# Christmas_Star.net
KiCad netlist of a schematic drawn in EAGLE
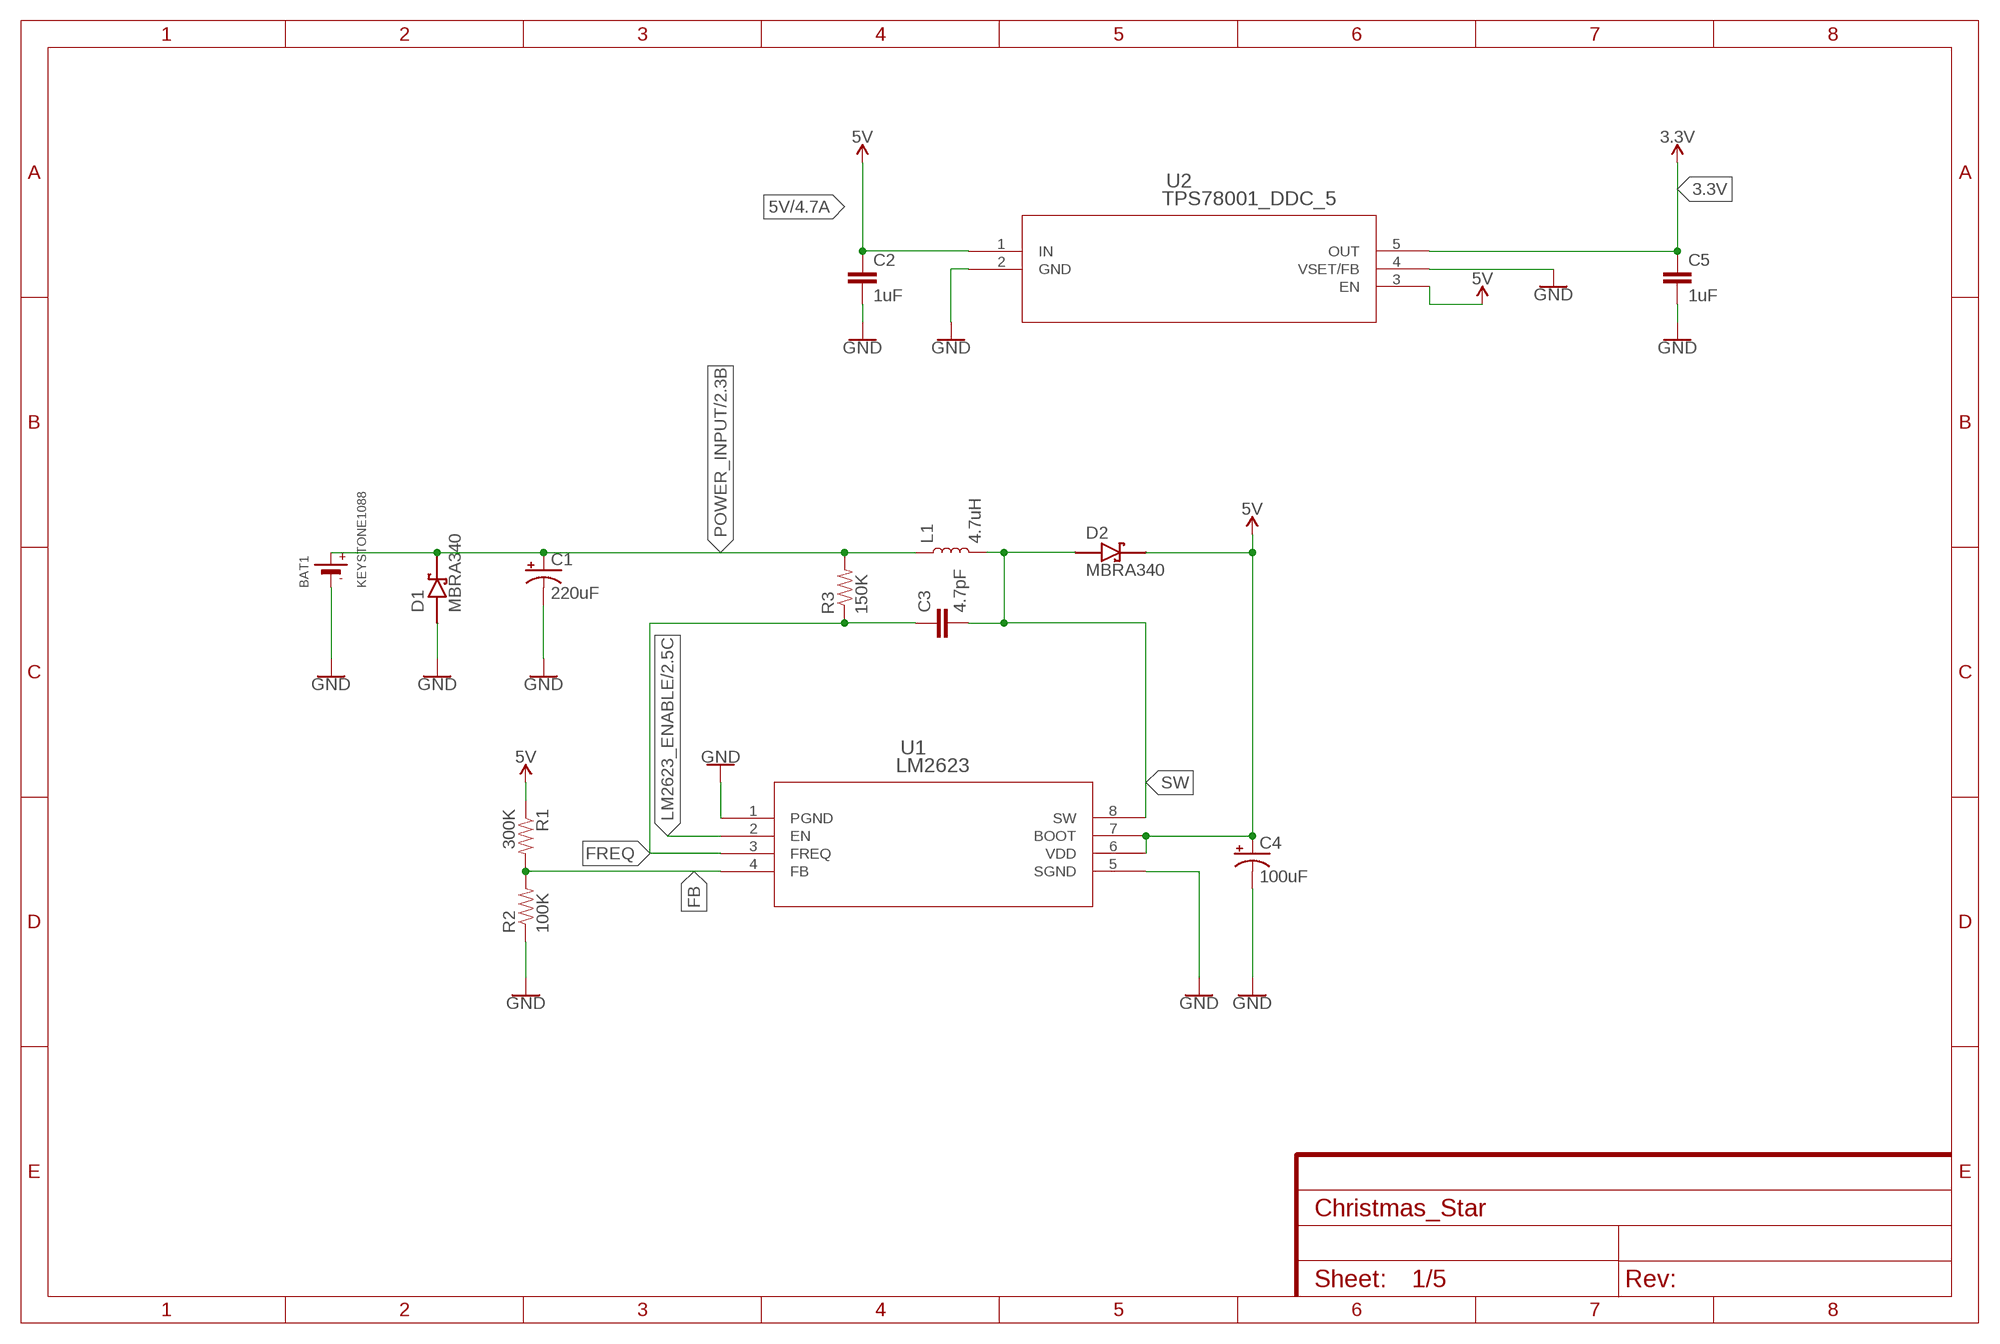
[diagram p0: schematic, sheet 1]
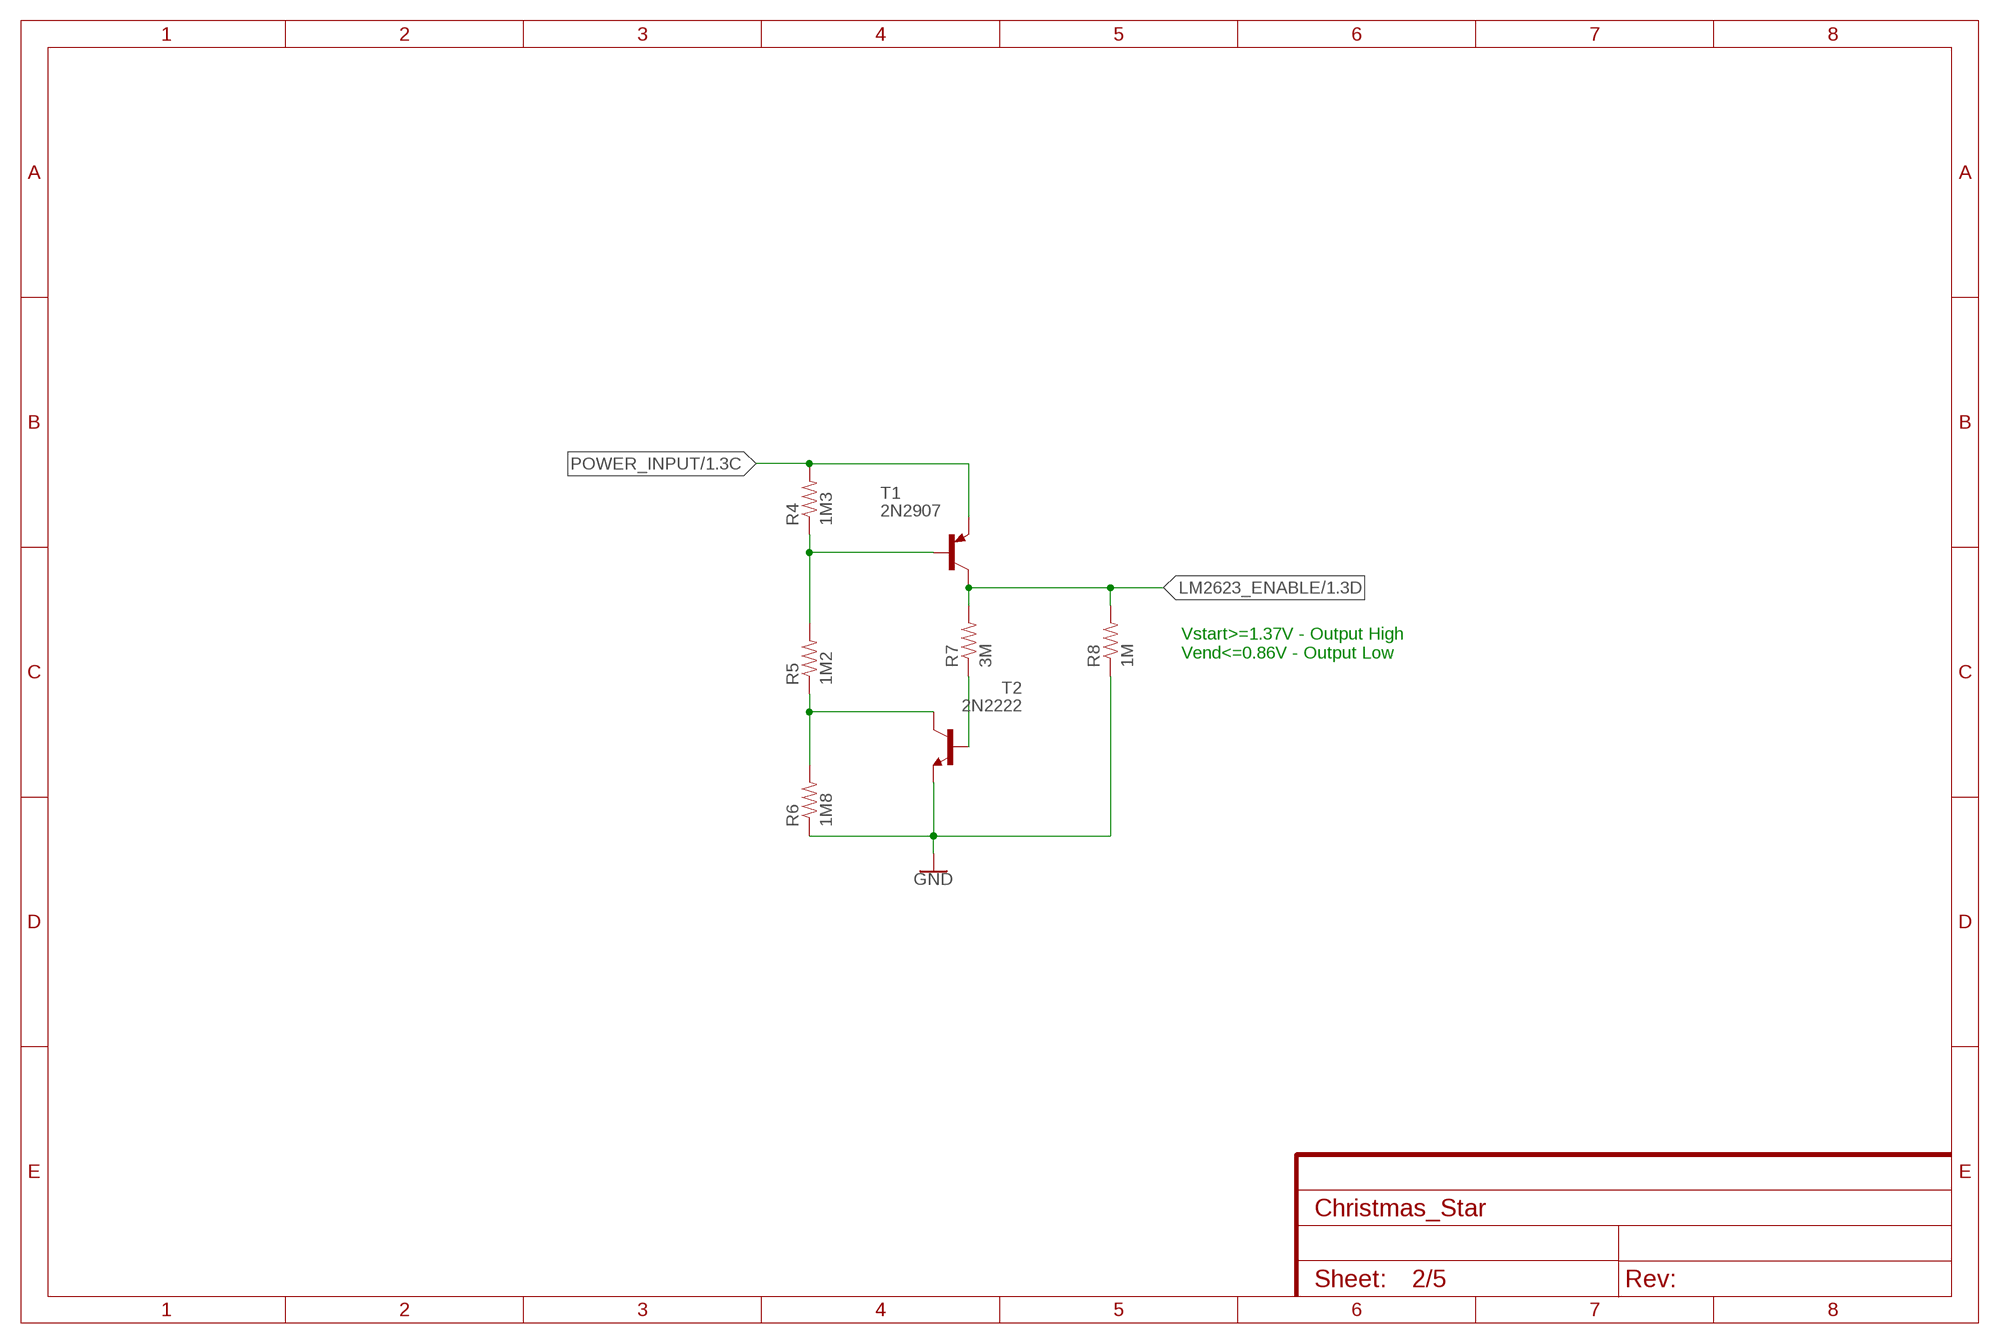
[diagram p1: schematic, sheet 2]
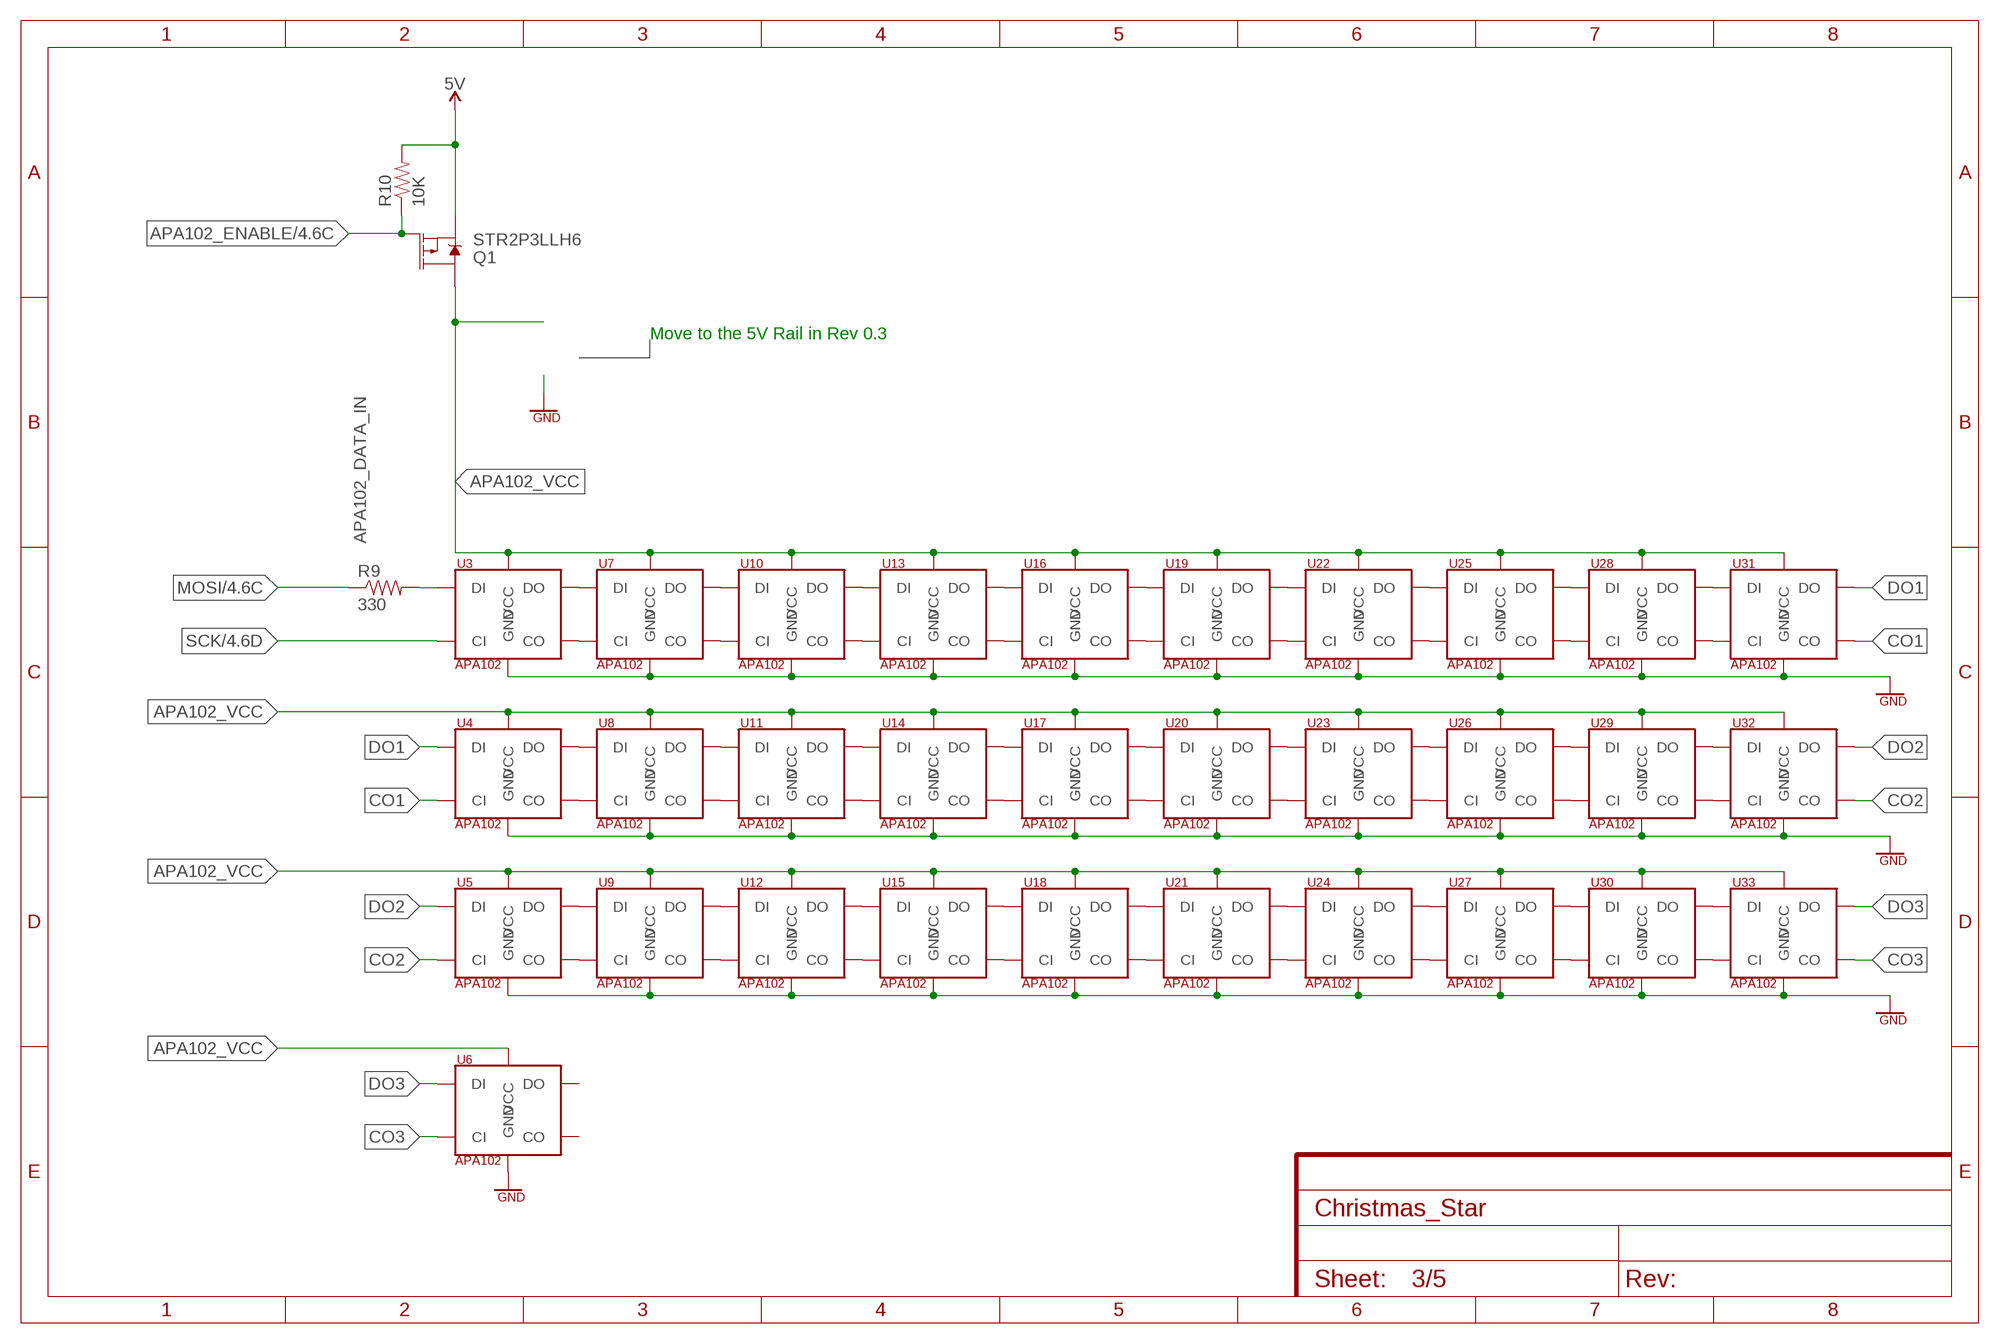
[diagram p2: schematic, sheet 3]
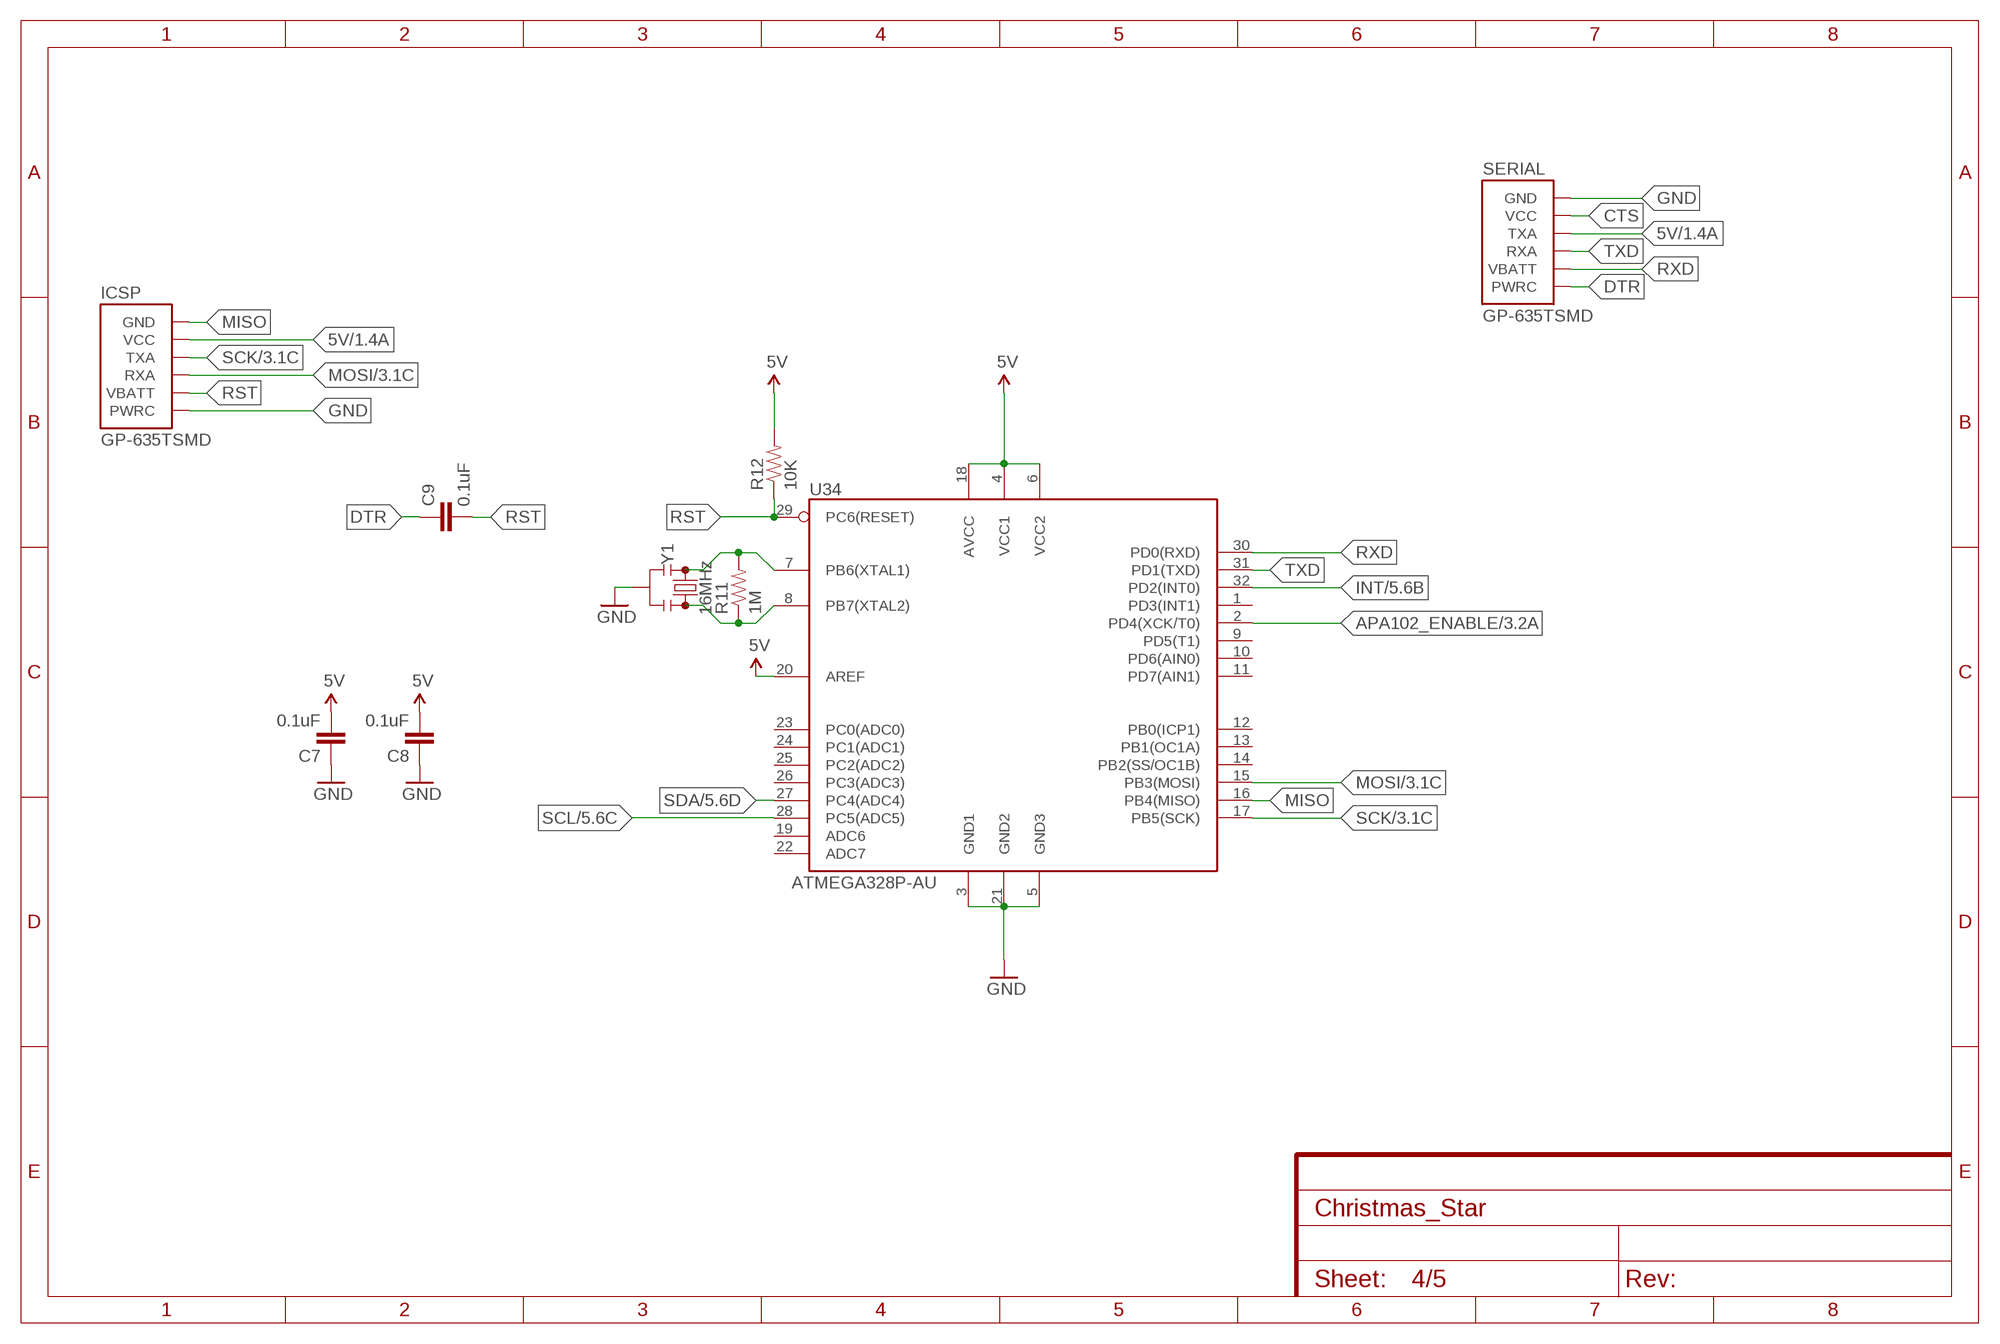
[diagram p3: schematic, sheet 4]
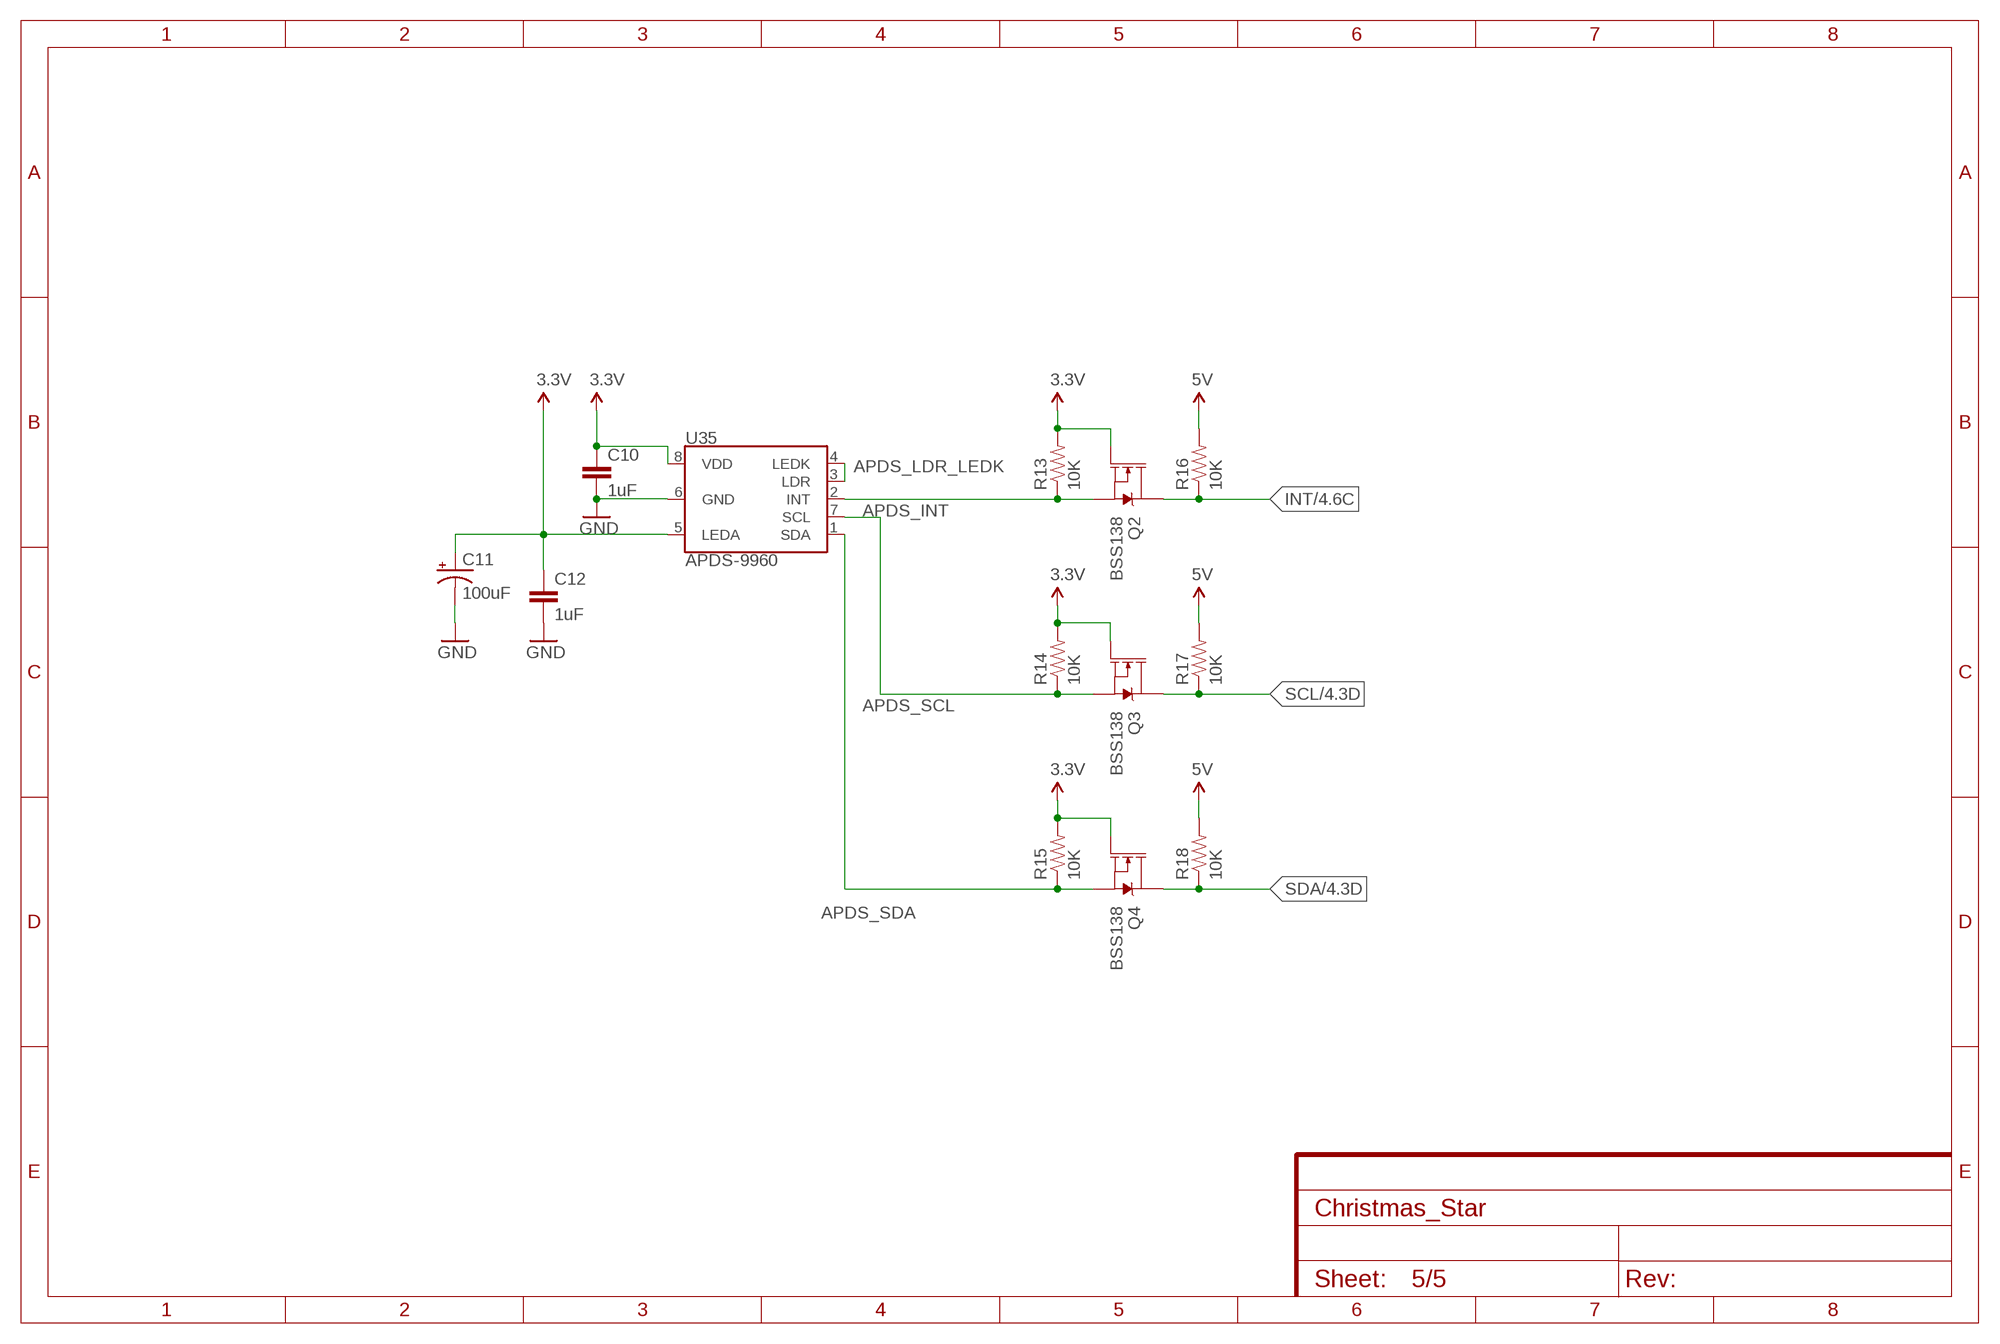
[diagram p4: schematic, sheet 5]

(export (version "E")
  (design (tool "Eeschema 10.0.6"))
  (components
    (comp (ref "Q1")
      (value "STR2P3LLH6")
      (footprint "eagle-import:SOT23-3")
      (libsource (lib "eagle-import") (part "MOSFET_PCH-IRLML2244"))
    )
    (comp (ref "R9")
      (value "330")
      (footprint "eagle-import:0603-RES")
      (libsource (lib "eagle-import") (part "RESISTOR0603-RES"))
    )
    (comp (ref "R10")
      (value "10K")
      (footprint "eagle-import:0603-RES")
      (libsource (lib "eagle-import") (part "RESISTOR0603-RES"))
    )
    (comp (ref "U3")
      (value "APA102")
      (footprint "eagle-import:APA102_2020")
      (libsource (lib "eagle-import") (part "APA1022020"))
    )
    (comp (ref "U4")
      (value "APA102")
      (footprint "eagle-import:APA102_2020")
      (libsource (lib "eagle-import") (part "APA1022020"))
    )
    (comp (ref "U5")
      (value "APA102")
      (footprint "eagle-import:APA102_2020")
      (libsource (lib "eagle-import") (part "APA1022020"))
    )
    (comp (ref "U6")
      (value "APA102")
      (footprint "eagle-import:APA102_2020")
      (libsource (lib "eagle-import") (part "APA1022020"))
    )
    (comp (ref "U7")
      (value "APA102")
      (footprint "eagle-import:APA102_2020")
      (libsource (lib "eagle-import") (part "APA1022020"))
    )
    (comp (ref "U8")
      (value "APA102")
      (footprint "eagle-import:APA102_2020")
      (libsource (lib "eagle-import") (part "APA1022020"))
    )
    (comp (ref "U9")
      (value "APA102")
      (footprint "eagle-import:APA102_2020")
      (libsource (lib "eagle-import") (part "APA1022020"))
    )
    (comp (ref "U10")
      (value "APA102")
      (footprint "eagle-import:APA102_2020")
      (libsource (lib "eagle-import") (part "APA1022020"))
    )
    (comp (ref "U11")
      (value "APA102")
      (footprint "eagle-import:APA102_2020")
      (libsource (lib "eagle-import") (part "APA1022020"))
    )
    (comp (ref "U12")
      (value "APA102")
      (footprint "eagle-import:APA102_2020")
      (libsource (lib "eagle-import") (part "APA1022020"))
    )
    (comp (ref "U13")
      (value "APA102")
      (footprint "eagle-import:APA102_2020")
      (libsource (lib "eagle-import") (part "APA1022020"))
    )
    (comp (ref "U14")
      (value "APA102")
      (footprint "eagle-import:APA102_2020")
      (libsource (lib "eagle-import") (part "APA1022020"))
    )
    (comp (ref "U15")
      (value "APA102")
      (footprint "eagle-import:APA102_2020")
      (libsource (lib "eagle-import") (part "APA1022020"))
    )
    (comp (ref "U16")
      (value "APA102")
      (footprint "eagle-import:APA102_2020")
      (libsource (lib "eagle-import") (part "APA1022020"))
    )
    (comp (ref "U17")
      (value "APA102")
      (footprint "eagle-import:APA102_2020")
      (libsource (lib "eagle-import") (part "APA1022020"))
    )
    (comp (ref "U18")
      (value "APA102")
      (footprint "eagle-import:APA102_2020")
      (libsource (lib "eagle-import") (part "APA1022020"))
    )
    (comp (ref "U19")
      (value "APA102")
      (footprint "eagle-import:APA102_2020")
      (libsource (lib "eagle-import") (part "APA1022020"))
    )
    (comp (ref "U20")
      (value "APA102")
      (footprint "eagle-import:APA102_2020")
      (libsource (lib "eagle-import") (part "APA1022020"))
    )
    (comp (ref "U21")
      (value "APA102")
      (footprint "eagle-import:APA102_2020")
      (libsource (lib "eagle-import") (part "APA1022020"))
    )
    (comp (ref "U22")
      (value "APA102")
      (footprint "eagle-import:APA102_2020")
      (libsource (lib "eagle-import") (part "APA1022020"))
    )
    (comp (ref "U23")
      (value "APA102")
      (footprint "eagle-import:APA102_2020")
      (libsource (lib "eagle-import") (part "APA1022020"))
    )
    (comp (ref "U24")
      (value "APA102")
      (footprint "eagle-import:APA102_2020")
      (libsource (lib "eagle-import") (part "APA1022020"))
    )
    (comp (ref "U25")
      (value "APA102")
      (footprint "eagle-import:APA102_2020")
      (libsource (lib "eagle-import") (part "APA1022020"))
    )
    (comp (ref "U26")
      (value "APA102")
      (footprint "eagle-import:APA102_2020")
      (libsource (lib "eagle-import") (part "APA1022020"))
    )
    (comp (ref "U27")
      (value "APA102")
      (footprint "eagle-import:APA102_2020")
      (libsource (lib "eagle-import") (part "APA1022020"))
    )
    (comp (ref "U28")
      (value "APA102")
      (footprint "eagle-import:APA102_2020")
      (libsource (lib "eagle-import") (part "APA1022020"))
    )
    (comp (ref "U29")
      (value "APA102")
      (footprint "eagle-import:APA102_2020")
      (libsource (lib "eagle-import") (part "APA1022020"))
    )
    (comp (ref "U30")
      (value "APA102")
      (footprint "eagle-import:APA102_2020")
      (libsource (lib "eagle-import") (part "APA1022020"))
    )
    (comp (ref "U31")
      (value "APA102")
      (footprint "eagle-import:APA102_2020")
      (libsource (lib "eagle-import") (part "APA1022020"))
    )
    (comp (ref "U32")
      (value "APA102")
      (footprint "eagle-import:APA102_2020")
      (libsource (lib "eagle-import") (part "APA1022020"))
    )
    (comp (ref "U33")
      (value "APA102")
      (footprint "eagle-import:APA102_2020")
      (libsource (lib "eagle-import") (part "APA1022020"))
    )
    (comp (ref "C10")
      (value "1uF")
      (footprint "eagle-import:0603-CAP")
      (libsource (lib "eagle-import") (part "SparkFun-Passives_CAP0603-CAP"))
    )
    (comp (ref "C11")
      (value "100uF")
      (footprint "eagle-import:EIA3216-KIT")
      (libsource (lib "eagle-import") (part "CAP_POL1206-KIT"))
    )
    (comp (ref "C12")
      (value "1uF")
      (footprint "eagle-import:0603-CAP")
      (libsource (lib "eagle-import") (part "SparkFun-Passives_CAP0603-CAP"))
    )
    (comp (ref "Q2")
      (value "BSS138")
      (footprint "eagle-import:SOT23-3")
      (libsource (lib "eagle-import") (part "MOSFET-NCH-BSS138"))
    )
    (comp (ref "Q3")
      (value "BSS138")
      (footprint "eagle-import:SOT23-3")
      (libsource (lib "eagle-import") (part "MOSFET-NCH-BSS138"))
    )
    (comp (ref "Q4")
      (value "BSS138")
      (footprint "eagle-import:SOT23-3")
      (libsource (lib "eagle-import") (part "MOSFET-NCH-BSS138"))
    )
    (comp (ref "R13")
      (value "10K")
      (footprint "eagle-import:0603-RES")
      (libsource (lib "eagle-import") (part "RESISTOR0603-RES"))
    )
    (comp (ref "R14")
      (value "10K")
      (footprint "eagle-import:0603-RES")
      (libsource (lib "eagle-import") (part "RESISTOR0603-RES"))
    )
    (comp (ref "R15")
      (value "10K")
      (footprint "eagle-import:0603-RES")
      (libsource (lib "eagle-import") (part "RESISTOR0603-RES"))
    )
    (comp (ref "R16")
      (value "10K")
      (footprint "eagle-import:0603-RES")
      (libsource (lib "eagle-import") (part "RESISTOR0603-RES"))
    )
    (comp (ref "R17")
      (value "10K")
      (footprint "eagle-import:0603-RES")
      (libsource (lib "eagle-import") (part "RESISTOR0603-RES"))
    )
    (comp (ref "R18")
      (value "10K")
      (footprint "eagle-import:0603-RES")
      (libsource (lib "eagle-import") (part "RESISTOR0603-RES"))
    )
    (comp (ref "U35")
      (value "APDS-9960")
      (footprint "eagle-import:APDS-9960")
      (libsource (lib "eagle-import") (part "APDS-9960"))
    )
    (comp (ref "BAT1")
      (value "KEYSTONE1088")
      (footprint "eagle-import:KEYSTONE1088")
      (libsource (lib "eagle-import") (part "KEYSTONE1088"))
    )
    (comp (ref "C1")
      (value "220uF")
      (footprint "eagle-import:EIA3528-KIT")
      (libsource (lib "eagle-import") (part "SparkFun-Passives_CAP_POL3528-KIT"))
    )
    (comp (ref "C2")
      (value "1uF")
      (footprint "eagle-import:0603-CAP")
      (libsource (lib "eagle-import") (part "SparkFun-Passives_CAP0603-CAP"))
    )
    (comp (ref "C3")
      (value "4.7pF")
      (footprint "eagle-import:0603-CAP")
      (libsource (lib "eagle-import") (part "CAP0603-CAP"))
    )
    (comp (ref "C4")
      (value "100uF")
      (footprint "eagle-import:EIA3216-KIT")
      (libsource (lib "eagle-import") (part "SparkFun-Passives_CAP_POL1206-KIT"))
    )
    (comp (ref "C5")
      (value "1uF")
      (footprint "eagle-import:0603-CAP")
      (libsource (lib "eagle-import") (part "SparkFun-Passives_CAP0603-CAP"))
    )
    (comp (ref "D1")
      (value "MBRA340")
      (footprint "eagle-import:DIOM4427X270N")
      (fields (field (name "MANUFACTURER") "Fairchild Semiconductor"))
      (libsource (lib "eagle-import") (part "SS12"))
    )
    (comp (ref "D2")
      (value "MBRA340")
      (footprint "eagle-import:DIOM4427X270N")
      (fields (field (name "MANUFACTURER") "Fairchild Semiconductor"))
      (libsource (lib "eagle-import") (part "SS12"))
    )
    (comp (ref "L1")
      (value "4.7uH")
      (footprint "eagle-import:LTF5022")
      (libsource (lib "eagle-import") (part "INDUCTOR"))
    )
    (comp (ref "R1")
      (value "300K")
      (footprint "eagle-import:0603-RES")
      (libsource (lib "eagle-import") (part "RESISTOR0603-RES"))
    )
    (comp (ref "R2")
      (value "100K")
      (footprint "eagle-import:0603-RES")
      (libsource (lib "eagle-import") (part "RESISTOR0603-RES"))
    )
    (comp (ref "R3")
      (value "150K")
      (footprint "eagle-import:0603-RES")
      (libsource (lib "eagle-import") (part "RESISTOR0603-RES"))
    )
    (comp (ref "U1")
      (value "LM2623")
      (footprint "eagle-import:MUA08A")
      (fields (field (name "MANUFACTURER_PART_NUMBER") "lm2623ammnopb"))
      (libsource (lib "eagle-import") (part "LM2623_DGK_8"))
    )
    (comp (ref "U2")
      (value "TPS78001_DDC_5")
      (footprint "eagle-import:DDC5")
      (fields
        (field (name "GENERIC_PART_NUMBER") "TPS78001")
        (field (name "MANUFACTURER") "Texas Instruments")
        (field (name "MANUFACTURER_PART_NUMBER") "tps78001_ddc_5")
      )
      (libsource (lib "eagle-import") (part "TPS78001_DDC_5"))
    )
    (comp (ref "R4")
      (value "1M3")
      (footprint "eagle-import:0603-RES")
      (libsource (lib "eagle-import") (part "RESISTOR0603-RES"))
    )
    (comp (ref "R5")
      (value "1M2")
      (footprint "eagle-import:0603-RES")
      (libsource (lib "eagle-import") (part "RESISTOR0603-RES"))
    )
    (comp (ref "R6")
      (value "1M8")
      (footprint "eagle-import:0603-RES")
      (libsource (lib "eagle-import") (part "RESISTOR0603-RES"))
    )
    (comp (ref "R7")
      (value "3M")
      (footprint "eagle-import:0603-RES")
      (libsource (lib "eagle-import") (part "RESISTOR0603-RES"))
    )
    (comp (ref "R8")
      (value "1M")
      (footprint "eagle-import:0603-RES")
      (libsource (lib "eagle-import") (part "RESISTOR0603-RES"))
    )
    (comp (ref "T1")
      (value "2N2907")
      (footprint "eagle-import:SOT23-BEC")
      (libsource (lib "eagle-import") (part "-PNP-SOT23-BECMMBT2907ALT1"))
    )
    (comp (ref "T2")
      (value "2N2222")
      (footprint "eagle-import:SOT23-BEC")
      (libsource (lib "eagle-import") (part "-NPN-SOT23-BECMMBT2222ALT1"))
    )
    (comp (ref "C7")
      (value "0.1uF")
      (footprint "eagle-import:0603-CAP")
      (libsource (lib "eagle-import") (part "SparkFun-Passives_CAP0603-CAP"))
    )
    (comp (ref "C8")
      (value "0.1uF")
      (footprint "eagle-import:0603-CAP")
      (libsource (lib "eagle-import") (part "SparkFun-Passives_CAP0603-CAP"))
    )
    (comp (ref "C9")
      (value "0.1uF")
      (footprint "eagle-import:0603-CAP")
      (libsource (lib "eagle-import") (part "SparkFun-Passives_CAP0603-CAP"))
    )
    (comp (ref "ICSP")
      (value "GP-635TSMD")
      (footprint "eagle-import:GP-635T")
      (libsource (lib "eagle-import") (part "GP-635TSMD"))
    )
    (comp (ref "R11")
      (value "1M")
      (footprint "eagle-import:0603-RES")
      (libsource (lib "eagle-import") (part "RESISTOR0603-RES"))
    )
    (comp (ref "R12")
      (value "10K")
      (footprint "eagle-import:0603-RES")
      (libsource (lib "eagle-import") (part "RESISTOR0603-RES"))
    )
    (comp (ref "SERIAL")
      (value "GP-635TSMD")
      (footprint "eagle-import:GP-635T")
      (libsource (lib "eagle-import") (part "GP-635TSMD"))
    )
    (comp (ref "U34")
      (value "ATMEGA328P-AU")
      (footprint "eagle-import:TQFP32")
      (libsource (lib "eagle-import") (part "ATMEGA328P-AU"))
    )
    (comp (ref "Y1")
      (value "16MHz")
      (footprint "eagle-import:RESONATOR-SMD-3.2X1.3")
      (libsource (lib "eagle-import") (part "RESONATOR-16MHZSMD_3.2X1.3"))
    )
  )
  (nets
    (net (code "1") (name "3.3V") (class "Default")
      (node (ref "C10") (pin "1") (pinfunction "1_1") (pintype "passive"))
      (node (ref "C11") (pin "A") (pinfunction "+_A") (pintype "passive"))
      (node (ref "C12") (pin "1") (pinfunction "1_1") (pintype "passive"))
      (node (ref "C5") (pin "1") (pinfunction "1_1") (pintype "passive"))
      (node (ref "Q2") (pin "1") (pinfunction "G_1") (pintype "bidirectional"))
      (node (ref "Q3") (pin "1") (pinfunction "G_1") (pintype "bidirectional"))
      (node (ref "Q4") (pin "1") (pinfunction "G_1") (pintype "bidirectional"))
      (node (ref "R13") (pin "2") (pinfunction "2_2") (pintype "passive"))
      (node (ref "R14") (pin "2") (pinfunction "2_2") (pintype "passive"))
      (node (ref "R15") (pin "2") (pinfunction "2_2") (pintype "passive"))
      (node (ref "U2") (pin "5") (pinfunction "OUT_5") (pintype "output"))
      (node (ref "U35") (pin "5") (pinfunction "LEDA_5") (pintype "bidirectional"))
      (node (ref "U35") (pin "8") (pinfunction "VDD_8") (pintype "bidirectional"))
    )
    (net (code "2") (name "5V") (class "Default")
      (node (ref "C2") (pin "1") (pinfunction "1_1") (pintype "passive"))
      (node (ref "C4") (pin "A") (pinfunction "+_A") (pintype "passive"))
      (node (ref "C7") (pin "2") (pinfunction "2_2") (pintype "passive"))
      (node (ref "C8") (pin "2") (pinfunction "2_2") (pintype "passive"))
      (node (ref "D2") (pin "C") (pinfunction "C_C") (pintype "passive"))
      (node (ref "ICSP") (pin "2") (pinfunction "VCC_2") (pintype "power_in"))
      (node (ref "Q1") (pin "2") (pinfunction "S_2") (pintype "bidirectional"))
      (node (ref "R1") (pin "1") (pinfunction "1_1") (pintype "passive"))
      (node (ref "R10") (pin "2") (pinfunction "2_2") (pintype "passive"))
      (node (ref "R12") (pin "2") (pinfunction "2_2") (pintype "passive"))
      (node (ref "R16") (pin "2") (pinfunction "2_2") (pintype "passive"))
      (node (ref "R17") (pin "2") (pinfunction "2_2") (pintype "passive"))
      (node (ref "R18") (pin "2") (pinfunction "2_2") (pintype "passive"))
      (node (ref "SERIAL") (pin "3") (pinfunction "TXA_3") (pintype "output"))
      (node (ref "U1") (pin "6") (pinfunction "VDD_6") (pintype "power_in"))
      (node (ref "U1") (pin "7") (pinfunction "BOOT_7") (pintype "passive"))
      (node (ref "U2") (pin "1") (pinfunction "IN_1") (pintype "input"))
      (node (ref "U2") (pin "3") (pinfunction "EN_3") (pintype "passive"))
      (node (ref "U34") (pin "18") (pinfunction "AVCC_18") (pintype "bidirectional"))
      (node (ref "U34") (pin "20") (pinfunction "AREF_20") (pintype "bidirectional"))
      (node (ref "U34") (pin "4") (pinfunction "VCC1_4") (pintype "bidirectional"))
      (node (ref "U34") (pin "6") (pinfunction "VCC2_6") (pintype "bidirectional"))
    )
    (net (code "3") (name "APA102_DATA_IN") (class "Default")
      (node (ref "R9") (pin "2") (pinfunction "2_2") (pintype "passive"))
      (node (ref "U3") (pin "D_IN") (pinfunction "DI_D_IN") (pintype "input"))
    )
    (net (code "4") (name "APA102_ENABLE") (class "Default")
      (node (ref "Q1") (pin "1") (pinfunction "G_1") (pintype "bidirectional"))
      (node (ref "R10") (pin "1") (pinfunction "1_1") (pintype "passive"))
      (node (ref "U34") (pin "2") (pinfunction "PD4(XCK/T0)_2") (pintype "bidirectional"))
    )
    (net (code "5") (name "APA102_VCC") (class "Default")
      (node (ref "Q1") (pin "3") (pinfunction "D_3") (pintype "bidirectional"))
      (node (ref "U10") (pin "VCC") (pinfunction "VCC_VCC") (pintype "power_in"))
      (node (ref "U11") (pin "VCC") (pinfunction "VCC_VCC") (pintype "power_in"))
      (node (ref "U12") (pin "VCC") (pinfunction "VCC_VCC") (pintype "power_in"))
      (node (ref "U13") (pin "VCC") (pinfunction "VCC_VCC") (pintype "power_in"))
      (node (ref "U14") (pin "VCC") (pinfunction "VCC_VCC") (pintype "power_in"))
      (node (ref "U15") (pin "VCC") (pinfunction "VCC_VCC") (pintype "power_in"))
      (node (ref "U16") (pin "VCC") (pinfunction "VCC_VCC") (pintype "power_in"))
      (node (ref "U17") (pin "VCC") (pinfunction "VCC_VCC") (pintype "power_in"))
      (node (ref "U18") (pin "VCC") (pinfunction "VCC_VCC") (pintype "power_in"))
      (node (ref "U19") (pin "VCC") (pinfunction "VCC_VCC") (pintype "power_in"))
      (node (ref "U20") (pin "VCC") (pinfunction "VCC_VCC") (pintype "power_in"))
      (node (ref "U21") (pin "VCC") (pinfunction "VCC_VCC") (pintype "power_in"))
      (node (ref "U22") (pin "VCC") (pinfunction "VCC_VCC") (pintype "power_in"))
      (node (ref "U23") (pin "VCC") (pinfunction "VCC_VCC") (pintype "power_in"))
      (node (ref "U24") (pin "VCC") (pinfunction "VCC_VCC") (pintype "power_in"))
      (node (ref "U25") (pin "VCC") (pinfunction "VCC_VCC") (pintype "power_in"))
      (node (ref "U26") (pin "VCC") (pinfunction "VCC_VCC") (pintype "power_in"))
      (node (ref "U27") (pin "VCC") (pinfunction "VCC_VCC") (pintype "power_in"))
      (node (ref "U28") (pin "VCC") (pinfunction "VCC_VCC") (pintype "power_in"))
      (node (ref "U29") (pin "VCC") (pinfunction "VCC_VCC") (pintype "power_in"))
      (node (ref "U3") (pin "VCC") (pinfunction "VCC_VCC") (pintype "power_in"))
      (node (ref "U30") (pin "VCC") (pinfunction "VCC_VCC") (pintype "power_in"))
      (node (ref "U31") (pin "VCC") (pinfunction "VCC_VCC") (pintype "power_in"))
      (node (ref "U32") (pin "VCC") (pinfunction "VCC_VCC") (pintype "power_in"))
      (node (ref "U33") (pin "VCC") (pinfunction "VCC_VCC") (pintype "power_in"))
      (node (ref "U4") (pin "VCC") (pinfunction "VCC_VCC") (pintype "power_in"))
      (node (ref "U5") (pin "VCC") (pinfunction "VCC_VCC") (pintype "power_in"))
      (node (ref "U6") (pin "VCC") (pinfunction "VCC_VCC") (pintype "power_in"))
      (node (ref "U7") (pin "VCC") (pinfunction "VCC_VCC") (pintype "power_in"))
      (node (ref "U8") (pin "VCC") (pinfunction "VCC_VCC") (pintype "power_in"))
      (node (ref "U9") (pin "VCC") (pinfunction "VCC_VCC") (pintype "power_in"))
    )
    (net (code "6") (name "APDS_INT") (class "Default")
      (node (ref "Q2") (pin "2") (pinfunction "S_2") (pintype "bidirectional"))
      (node (ref "R13") (pin "1") (pinfunction "1_1") (pintype "passive"))
      (node (ref "U35") (pin "2") (pinfunction "INT_2") (pintype "bidirectional"))
    )
    (net (code "7") (name "APDS_LDR_LEDK") (class "Default")
      (node (ref "U35") (pin "3") (pinfunction "LDR_3") (pintype "bidirectional"))
      (node (ref "U35") (pin "4") (pinfunction "LEDK_4") (pintype "bidirectional"))
    )
    (net (code "8") (name "APDS_SCL") (class "Default")
      (node (ref "Q3") (pin "2") (pinfunction "S_2") (pintype "bidirectional"))
      (node (ref "R14") (pin "1") (pinfunction "1_1") (pintype "passive"))
      (node (ref "U35") (pin "7") (pinfunction "SCL_7") (pintype "bidirectional"))
    )
    (net (code "9") (name "APDS_SDA") (class "Default")
      (node (ref "Q4") (pin "2") (pinfunction "S_2") (pintype "bidirectional"))
      (node (ref "R15") (pin "1") (pinfunction "1_1") (pintype "passive"))
      (node (ref "U35") (pin "1") (pinfunction "SDA_1") (pintype "bidirectional"))
    )
    (net (code "10") (name "CO1") (class "Default")
      (node (ref "U31") (pin "CL_OUT") (pinfunction "CO_CL_OUT") (pintype "output"))
      (node (ref "U4") (pin "C_IN") (pinfunction "CI_C_IN") (pintype "input"))
    )
    (net (code "11") (name "CO2") (class "Default")
      (node (ref "U32") (pin "CL_OUT") (pinfunction "CO_CL_OUT") (pintype "output"))
      (node (ref "U5") (pin "C_IN") (pinfunction "CI_C_IN") (pintype "input"))
    )
    (net (code "12") (name "CO3") (class "Default")
      (node (ref "U33") (pin "CL_OUT") (pinfunction "CO_CL_OUT") (pintype "output"))
      (node (ref "U6") (pin "C_IN") (pinfunction "CI_C_IN") (pintype "input"))
    )
    (net (code "13") (name "CTS") (class "Default")
      (node (ref "SERIAL") (pin "2") (pinfunction "VCC_2") (pintype "power_in"))
    )
    (net (code "14") (name "DO1") (class "Default")
      (node (ref "U31") (pin "D_OUT") (pinfunction "DO_D_OUT") (pintype "output"))
      (node (ref "U4") (pin "D_IN") (pinfunction "DI_D_IN") (pintype "input"))
    )
    (net (code "15") (name "DO2") (class "Default")
      (node (ref "U32") (pin "D_OUT") (pinfunction "DO_D_OUT") (pintype "output"))
      (node (ref "U5") (pin "D_IN") (pinfunction "DI_D_IN") (pintype "input"))
    )
    (net (code "16") (name "DO3") (class "Default")
      (node (ref "U33") (pin "D_OUT") (pinfunction "DO_D_OUT") (pintype "output"))
      (node (ref "U6") (pin "D_IN") (pinfunction "DI_D_IN") (pintype "input"))
    )
    (net (code "17") (name "DTR") (class "Default")
      (node (ref "C9") (pin "1") (pinfunction "1_1") (pintype "passive"))
      (node (ref "SERIAL") (pin "6") (pinfunction "PWRC_6") (pintype "input"))
    )
    (net (code "18") (name "FB") (class "Default")
      (node (ref "R1") (pin "2") (pinfunction "2_2") (pintype "passive"))
      (node (ref "R2") (pin "2") (pinfunction "2_2") (pintype "passive"))
      (node (ref "U1") (pin "4") (pinfunction "FB_4") (pintype "input"))
    )
    (net (code "19") (name "FREQ") (class "Default")
      (node (ref "C3") (pin "1") (pinfunction "1_1") (pintype "passive"))
      (node (ref "R3") (pin "1") (pinfunction "1_1") (pintype "passive"))
      (node (ref "U1") (pin "3") (pinfunction "FREQ_3") (pintype "input"))
    )
    (net (code "20") (name "GND") (class "Default")
      (node (ref "BAT1") (pin "-") (pinfunction "-_-") (pintype "passive"))
      (node (ref "C1") (pin "C") (pinfunction "-_C") (pintype "passive"))
      (node (ref "C10") (pin "2") (pinfunction "2_2") (pintype "passive"))
      (node (ref "C11") (pin "C") (pinfunction "-_C") (pintype "passive"))
      (node (ref "C12") (pin "2") (pinfunction "2_2") (pintype "passive"))
      (node (ref "C2") (pin "2") (pinfunction "2_2") (pintype "passive"))
      (node (ref "C4") (pin "C") (pinfunction "-_C") (pintype "passive"))
      (node (ref "C5") (pin "2") (pinfunction "2_2") (pintype "passive"))
      (node (ref "C7") (pin "1") (pinfunction "1_1") (pintype "passive"))
      (node (ref "C8") (pin "1") (pinfunction "1_1") (pintype "passive"))
      (node (ref "D1") (pin "A") (pinfunction "A_A") (pintype "passive"))
      (node (ref "ICSP") (pin "6") (pinfunction "PWRC_6") (pintype "input"))
      (node (ref "R2") (pin "1") (pinfunction "1_1") (pintype "passive"))
      (node (ref "R6") (pin "1") (pinfunction "1_1") (pintype "passive"))
      (node (ref "R8") (pin "1") (pinfunction "1_1") (pintype "passive"))
      (node (ref "SERIAL") (pin "1") (pinfunction "GND_1") (pintype "power_in"))
      (node (ref "T2") (pin "E") (pinfunction "E_E") (pintype "passive"))
      (node (ref "U1") (pin "1") (pinfunction "PGND_1") (pintype "power_in"))
      (node (ref "U1") (pin "5") (pinfunction "SGND_5") (pintype "power_in"))
      (node (ref "U10") (pin "GND") (pinfunction "GND_GND") (pintype "power_in"))
      (node (ref "U11") (pin "GND") (pinfunction "GND_GND") (pintype "power_in"))
      (node (ref "U12") (pin "GND") (pinfunction "GND_GND") (pintype "power_in"))
      (node (ref "U13") (pin "GND") (pinfunction "GND_GND") (pintype "power_in"))
      (node (ref "U14") (pin "GND") (pinfunction "GND_GND") (pintype "power_in"))
      (node (ref "U15") (pin "GND") (pinfunction "GND_GND") (pintype "power_in"))
      (node (ref "U16") (pin "GND") (pinfunction "GND_GND") (pintype "power_in"))
      (node (ref "U17") (pin "GND") (pinfunction "GND_GND") (pintype "power_in"))
      (node (ref "U18") (pin "GND") (pinfunction "GND_GND") (pintype "power_in"))
      (node (ref "U19") (pin "GND") (pinfunction "GND_GND") (pintype "power_in"))
      (node (ref "U2") (pin "2") (pinfunction "GND_2") (pintype "power_in"))
      (node (ref "U2") (pin "4") (pinfunction "VSET/FB_4") (pintype "passive"))
      (node (ref "U20") (pin "GND") (pinfunction "GND_GND") (pintype "power_in"))
      (node (ref "U21") (pin "GND") (pinfunction "GND_GND") (pintype "power_in"))
      (node (ref "U22") (pin "GND") (pinfunction "GND_GND") (pintype "power_in"))
      (node (ref "U23") (pin "GND") (pinfunction "GND_GND") (pintype "power_in"))
      (node (ref "U24") (pin "GND") (pinfunction "GND_GND") (pintype "power_in"))
      (node (ref "U25") (pin "GND") (pinfunction "GND_GND") (pintype "power_in"))
      (node (ref "U26") (pin "GND") (pinfunction "GND_GND") (pintype "power_in"))
      (node (ref "U27") (pin "GND") (pinfunction "GND_GND") (pintype "power_in"))
      (node (ref "U28") (pin "GND") (pinfunction "GND_GND") (pintype "power_in"))
      (node (ref "U29") (pin "GND") (pinfunction "GND_GND") (pintype "power_in"))
      (node (ref "U3") (pin "GND") (pinfunction "GND_GND") (pintype "power_in"))
      (node (ref "U30") (pin "GND") (pinfunction "GND_GND") (pintype "power_in"))
      (node (ref "U31") (pin "GND") (pinfunction "GND_GND") (pintype "power_in"))
      (node (ref "U32") (pin "GND") (pinfunction "GND_GND") (pintype "power_in"))
      (node (ref "U33") (pin "GND") (pinfunction "GND_GND") (pintype "power_in"))
      (node (ref "U34") (pin "21") (pinfunction "GND2_21") (pintype "bidirectional"))
      (node (ref "U34") (pin "3") (pinfunction "GND1_3") (pintype "bidirectional"))
      (node (ref "U34") (pin "5") (pinfunction "GND3_5") (pintype "bidirectional"))
      (node (ref "U35") (pin "6") (pinfunction "GND_6") (pintype "bidirectional"))
      (node (ref "U4") (pin "GND") (pinfunction "GND_GND") (pintype "power_in"))
      (node (ref "U5") (pin "GND") (pinfunction "GND_GND") (pintype "power_in"))
      (node (ref "U6") (pin "GND") (pinfunction "GND_GND") (pintype "power_in"))
      (node (ref "U7") (pin "GND") (pinfunction "GND_GND") (pintype "power_in"))
      (node (ref "U8") (pin "GND") (pinfunction "GND_GND") (pintype "power_in"))
      (node (ref "U9") (pin "GND") (pinfunction "GND_GND") (pintype "power_in"))
      (node (ref "Y1") (pin "2") (pinfunction "2_2") (pintype "passive"))
    )
    (net (code "21") (name "INT") (class "Default")
      (node (ref "Q2") (pin "3") (pinfunction "D_3") (pintype "bidirectional"))
      (node (ref "R16") (pin "1") (pinfunction "1_1") (pintype "passive"))
      (node (ref "U34") (pin "32") (pinfunction "PD2(INT0)_32") (pintype "bidirectional"))
    )
    (net (code "22") (name "LM2623_ENABLE") (class "Default")
      (node (ref "R7") (pin "2") (pinfunction "2_2") (pintype "passive"))
      (node (ref "R8") (pin "2") (pinfunction "2_2") (pintype "passive"))
      (node (ref "T1") (pin "C") (pinfunction "C_C") (pintype "passive"))
      (node (ref "U1") (pin "2") (pinfunction "EN_2") (pintype "input"))
    )
    (net (code "23") (name "MISO") (class "Default")
      (node (ref "ICSP") (pin "1") (pinfunction "GND_1") (pintype "power_in"))
      (node (ref "U34") (pin "16") (pinfunction "PB4(MISO)_16") (pintype "bidirectional"))
    )
    (net (code "24") (name "MOSI") (class "Default")
      (node (ref "ICSP") (pin "4") (pinfunction "RXA_4") (pintype "input"))
      (node (ref "R9") (pin "1") (pinfunction "1_1") (pintype "passive"))
      (node (ref "U34") (pin "15") (pinfunction "PB3(MOSI)_15") (pintype "bidirectional"))
    )
    (net (code "25") (name "Net-(R4-Pad1)") (class "Default")
      (node (ref "R4") (pin "1") (pinfunction "1_1") (pintype "passive"))
      (node (ref "R5") (pin "2") (pinfunction "2_2") (pintype "passive"))
      (node (ref "T1") (pin "B") (pinfunction "B_B") (pintype "passive"))
    )
    (net (code "26") (name "Net-(R5-Pad1)") (class "Default")
      (node (ref "R5") (pin "1") (pinfunction "1_1") (pintype "passive"))
      (node (ref "R6") (pin "2") (pinfunction "2_2") (pintype "passive"))
      (node (ref "T2") (pin "C") (pinfunction "C_C") (pintype "passive"))
    )
    (net (code "27") (name "Net-(R7-Pad1)") (class "Default")
      (node (ref "R7") (pin "1") (pinfunction "1_1") (pintype "passive"))
      (node (ref "T2") (pin "B") (pinfunction "B_B") (pintype "passive"))
    )
    (net (code "28") (name "Net-(U3-CO)") (class "Default")
      (node (ref "U3") (pin "CL_OUT") (pinfunction "CO_CL_OUT") (pintype "output"))
      (node (ref "U7") (pin "C_IN") (pinfunction "CI_C_IN") (pintype "input"))
    )
    (net (code "29") (name "Net-(U3-DO)") (class "Default")
      (node (ref "U3") (pin "D_OUT") (pinfunction "DO_D_OUT") (pintype "output"))
      (node (ref "U7") (pin "D_IN") (pinfunction "DI_D_IN") (pintype "input"))
    )
    (net (code "30") (name "Net-(U4-CO)") (class "Default")
      (node (ref "U4") (pin "CL_OUT") (pinfunction "CO_CL_OUT") (pintype "output"))
      (node (ref "U8") (pin "C_IN") (pinfunction "CI_C_IN") (pintype "input"))
    )
    (net (code "31") (name "Net-(U4-DO)") (class "Default")
      (node (ref "U4") (pin "D_OUT") (pinfunction "DO_D_OUT") (pintype "output"))
      (node (ref "U8") (pin "D_IN") (pinfunction "DI_D_IN") (pintype "input"))
    )
    (net (code "32") (name "Net-(U5-CO)") (class "Default")
      (node (ref "U5") (pin "CL_OUT") (pinfunction "CO_CL_OUT") (pintype "output"))
      (node (ref "U9") (pin "C_IN") (pinfunction "CI_C_IN") (pintype "input"))
    )
    (net (code "33") (name "Net-(U5-DO)") (class "Default")
      (node (ref "U5") (pin "D_OUT") (pinfunction "DO_D_OUT") (pintype "output"))
      (node (ref "U9") (pin "D_IN") (pinfunction "DI_D_IN") (pintype "input"))
    )
    (net (code "34") (name "Net-(U10-CI)") (class "Default")
      (node (ref "U10") (pin "C_IN") (pinfunction "CI_C_IN") (pintype "input"))
      (node (ref "U7") (pin "CL_OUT") (pinfunction "CO_CL_OUT") (pintype "output"))
    )
    (net (code "35") (name "Net-(U10-CO)") (class "Default")
      (node (ref "U10") (pin "CL_OUT") (pinfunction "CO_CL_OUT") (pintype "output"))
      (node (ref "U13") (pin "C_IN") (pinfunction "CI_C_IN") (pintype "input"))
    )
    (net (code "36") (name "Net-(U10-DI)") (class "Default")
      (node (ref "U10") (pin "D_IN") (pinfunction "DI_D_IN") (pintype "input"))
      (node (ref "U7") (pin "D_OUT") (pinfunction "DO_D_OUT") (pintype "output"))
    )
    (net (code "37") (name "Net-(U10-DO)") (class "Default")
      (node (ref "U10") (pin "D_OUT") (pinfunction "DO_D_OUT") (pintype "output"))
      (node (ref "U13") (pin "D_IN") (pinfunction "DI_D_IN") (pintype "input"))
    )
    (net (code "38") (name "Net-(U11-CI)") (class "Default")
      (node (ref "U11") (pin "C_IN") (pinfunction "CI_C_IN") (pintype "input"))
      (node (ref "U8") (pin "CL_OUT") (pinfunction "CO_CL_OUT") (pintype "output"))
    )
    (net (code "39") (name "Net-(U11-CO)") (class "Default")
      (node (ref "U11") (pin "CL_OUT") (pinfunction "CO_CL_OUT") (pintype "output"))
      (node (ref "U14") (pin "C_IN") (pinfunction "CI_C_IN") (pintype "input"))
    )
    (net (code "40") (name "Net-(U11-DI)") (class "Default")
      (node (ref "U11") (pin "D_IN") (pinfunction "DI_D_IN") (pintype "input"))
      (node (ref "U8") (pin "D_OUT") (pinfunction "DO_D_OUT") (pintype "output"))
    )
    (net (code "41") (name "Net-(U11-DO)") (class "Default")
      (node (ref "U11") (pin "D_OUT") (pinfunction "DO_D_OUT") (pintype "output"))
      (node (ref "U14") (pin "D_IN") (pinfunction "DI_D_IN") (pintype "input"))
    )
    (net (code "42") (name "Net-(U12-CI)") (class "Default")
      (node (ref "U12") (pin "C_IN") (pinfunction "CI_C_IN") (pintype "input"))
      (node (ref "U9") (pin "CL_OUT") (pinfunction "CO_CL_OUT") (pintype "output"))
    )
    (net (code "43") (name "Net-(U12-CO)") (class "Default")
      (node (ref "U12") (pin "CL_OUT") (pinfunction "CO_CL_OUT") (pintype "output"))
      (node (ref "U15") (pin "C_IN") (pinfunction "CI_C_IN") (pintype "input"))
    )
    (net (code "44") (name "Net-(U12-DI)") (class "Default")
      (node (ref "U12") (pin "D_IN") (pinfunction "DI_D_IN") (pintype "input"))
      (node (ref "U9") (pin "D_OUT") (pinfunction "DO_D_OUT") (pintype "output"))
    )
    (net (code "45") (name "Net-(U12-DO)") (class "Default")
      (node (ref "U12") (pin "D_OUT") (pinfunction "DO_D_OUT") (pintype "output"))
      (node (ref "U15") (pin "D_IN") (pinfunction "DI_D_IN") (pintype "input"))
    )
    (net (code "46") (name "Net-(U13-CO)") (class "Default")
      (node (ref "U13") (pin "CL_OUT") (pinfunction "CO_CL_OUT") (pintype "output"))
      (node (ref "U16") (pin "C_IN") (pinfunction "CI_C_IN") (pintype "input"))
    )
    (net (code "47") (name "Net-(U13-DO)") (class "Default")
      (node (ref "U13") (pin "D_OUT") (pinfunction "DO_D_OUT") (pintype "output"))
      (node (ref "U16") (pin "D_IN") (pinfunction "DI_D_IN") (pintype "input"))
    )
    (net (code "48") (name "Net-(U14-CO)") (class "Default")
      (node (ref "U14") (pin "CL_OUT") (pinfunction "CO_CL_OUT") (pintype "output"))
      (node (ref "U17") (pin "C_IN") (pinfunction "CI_C_IN") (pintype "input"))
    )
    (net (code "49") (name "Net-(U14-DO)") (class "Default")
      (node (ref "U14") (pin "D_OUT") (pinfunction "DO_D_OUT") (pintype "output"))
      (node (ref "U17") (pin "D_IN") (pinfunction "DI_D_IN") (pintype "input"))
    )
    (net (code "50") (name "Net-(U15-CO)") (class "Default")
      (node (ref "U15") (pin "CL_OUT") (pinfunction "CO_CL_OUT") (pintype "output"))
      (node (ref "U18") (pin "C_IN") (pinfunction "CI_C_IN") (pintype "input"))
    )
    (net (code "51") (name "Net-(U15-DO)") (class "Default")
      (node (ref "U15") (pin "D_OUT") (pinfunction "DO_D_OUT") (pintype "output"))
      (node (ref "U18") (pin "D_IN") (pinfunction "DI_D_IN") (pintype "input"))
    )
    (net (code "52") (name "Net-(U16-CO)") (class "Default")
      (node (ref "U16") (pin "CL_OUT") (pinfunction "CO_CL_OUT") (pintype "output"))
      (node (ref "U19") (pin "C_IN") (pinfunction "CI_C_IN") (pintype "input"))
    )
    (net (code "53") (name "Net-(U16-DO)") (class "Default")
      (node (ref "U16") (pin "D_OUT") (pinfunction "DO_D_OUT") (pintype "output"))
      (node (ref "U19") (pin "D_IN") (pinfunction "DI_D_IN") (pintype "input"))
    )
    (net (code "54") (name "Net-(U17-CO)") (class "Default")
      (node (ref "U17") (pin "CL_OUT") (pinfunction "CO_CL_OUT") (pintype "output"))
      (node (ref "U20") (pin "C_IN") (pinfunction "CI_C_IN") (pintype "input"))
    )
    (net (code "55") (name "Net-(U17-DO)") (class "Default")
      (node (ref "U17") (pin "D_OUT") (pinfunction "DO_D_OUT") (pintype "output"))
      (node (ref "U20") (pin "D_IN") (pinfunction "DI_D_IN") (pintype "input"))
    )
    (net (code "56") (name "Net-(U18-CO)") (class "Default")
      (node (ref "U18") (pin "CL_OUT") (pinfunction "CO_CL_OUT") (pintype "output"))
      (node (ref "U21") (pin "C_IN") (pinfunction "CI_C_IN") (pintype "input"))
    )
    (net (code "57") (name "Net-(U18-DO)") (class "Default")
      (node (ref "U18") (pin "D_OUT") (pinfunction "DO_D_OUT") (pintype "output"))
      (node (ref "U21") (pin "D_IN") (pinfunction "DI_D_IN") (pintype "input"))
    )
    (net (code "58") (name "Net-(U19-CO)") (class "Default")
      (node (ref "U19") (pin "CL_OUT") (pinfunction "CO_CL_OUT") (pintype "output"))
      (node (ref "U22") (pin "C_IN") (pinfunction "CI_C_IN") (pintype "input"))
    )
    (net (code "59") (name "Net-(U19-DO)") (class "Default")
      (node (ref "U19") (pin "D_OUT") (pinfunction "DO_D_OUT") (pintype "output"))
      (node (ref "U22") (pin "D_IN") (pinfunction "DI_D_IN") (pintype "input"))
    )
    (net (code "60") (name "Net-(U20-CO)") (class "Default")
      (node (ref "U20") (pin "CL_OUT") (pinfunction "CO_CL_OUT") (pintype "output"))
      (node (ref "U23") (pin "C_IN") (pinfunction "CI_C_IN") (pintype "input"))
    )
    (net (code "61") (name "Net-(U20-DO)") (class "Default")
      (node (ref "U20") (pin "D_OUT") (pinfunction "DO_D_OUT") (pintype "output"))
      (node (ref "U23") (pin "D_IN") (pinfunction "DI_D_IN") (pintype "input"))
    )
    (net (code "62") (name "Net-(U21-CO)") (class "Default")
      (node (ref "U21") (pin "CL_OUT") (pinfunction "CO_CL_OUT") (pintype "output"))
      (node (ref "U24") (pin "C_IN") (pinfunction "CI_C_IN") (pintype "input"))
    )
    (net (code "63") (name "Net-(U21-DO)") (class "Default")
      (node (ref "U21") (pin "D_OUT") (pinfunction "DO_D_OUT") (pintype "output"))
      (node (ref "U24") (pin "D_IN") (pinfunction "DI_D_IN") (pintype "input"))
    )
    (net (code "64") (name "Net-(U22-CO)") (class "Default")
      (node (ref "U22") (pin "CL_OUT") (pinfunction "CO_CL_OUT") (pintype "output"))
      (node (ref "U25") (pin "C_IN") (pinfunction "CI_C_IN") (pintype "input"))
    )
    (net (code "65") (name "Net-(U22-DO)") (class "Default")
      (node (ref "U22") (pin "D_OUT") (pinfunction "DO_D_OUT") (pintype "output"))
      (node (ref "U25") (pin "D_IN") (pinfunction "DI_D_IN") (pintype "input"))
    )
    (net (code "66") (name "Net-(U23-CO)") (class "Default")
      (node (ref "U23") (pin "CL_OUT") (pinfunction "CO_CL_OUT") (pintype "output"))
      (node (ref "U26") (pin "C_IN") (pinfunction "CI_C_IN") (pintype "input"))
    )
    (net (code "67") (name "Net-(U23-DO)") (class "Default")
      (node (ref "U23") (pin "D_OUT") (pinfunction "DO_D_OUT") (pintype "output"))
      (node (ref "U26") (pin "D_IN") (pinfunction "DI_D_IN") (pintype "input"))
    )
    (net (code "68") (name "Net-(U24-CO)") (class "Default")
      (node (ref "U24") (pin "CL_OUT") (pinfunction "CO_CL_OUT") (pintype "output"))
      (node (ref "U27") (pin "C_IN") (pinfunction "CI_C_IN") (pintype "input"))
    )
    (net (code "69") (name "Net-(U24-DO)") (class "Default")
      (node (ref "U24") (pin "D_OUT") (pinfunction "DO_D_OUT") (pintype "output"))
      (node (ref "U27") (pin "D_IN") (pinfunction "DI_D_IN") (pintype "input"))
    )
    (net (code "70") (name "Net-(U25-CO)") (class "Default")
      (node (ref "U25") (pin "CL_OUT") (pinfunction "CO_CL_OUT") (pintype "output"))
      (node (ref "U28") (pin "C_IN") (pinfunction "CI_C_IN") (pintype "input"))
    )
    (net (code "71") (name "Net-(U25-DO)") (class "Default")
      (node (ref "U25") (pin "D_OUT") (pinfunction "DO_D_OUT") (pintype "output"))
      (node (ref "U28") (pin "D_IN") (pinfunction "DI_D_IN") (pintype "input"))
    )
    (net (code "72") (name "Net-(U26-CO)") (class "Default")
      (node (ref "U26") (pin "CL_OUT") (pinfunction "CO_CL_OUT") (pintype "output"))
      (node (ref "U29") (pin "C_IN") (pinfunction "CI_C_IN") (pintype "input"))
    )
    (net (code "73") (name "Net-(U26-DO)") (class "Default")
      (node (ref "U26") (pin "D_OUT") (pinfunction "DO_D_OUT") (pintype "output"))
      (node (ref "U29") (pin "D_IN") (pinfunction "DI_D_IN") (pintype "input"))
    )
    (net (code "74") (name "Net-(U27-CO)") (class "Default")
      (node (ref "U27") (pin "CL_OUT") (pinfunction "CO_CL_OUT") (pintype "output"))
      (node (ref "U30") (pin "C_IN") (pinfunction "CI_C_IN") (pintype "input"))
    )
    (net (code "75") (name "Net-(U27-DO)") (class "Default")
      (node (ref "U27") (pin "D_OUT") (pinfunction "DO_D_OUT") (pintype "output"))
      (node (ref "U30") (pin "D_IN") (pinfunction "DI_D_IN") (pintype "input"))
    )
    (net (code "76") (name "Net-(U28-CO)") (class "Default")
      (node (ref "U28") (pin "CL_OUT") (pinfunction "CO_CL_OUT") (pintype "output"))
      (node (ref "U31") (pin "C_IN") (pinfunction "CI_C_IN") (pintype "input"))
    )
    (net (code "77") (name "Net-(U28-DO)") (class "Default")
      (node (ref "U28") (pin "D_OUT") (pinfunction "DO_D_OUT") (pintype "output"))
      (node (ref "U31") (pin "D_IN") (pinfunction "DI_D_IN") (pintype "input"))
    )
    (net (code "78") (name "Net-(U29-CO)") (class "Default")
      (node (ref "U29") (pin "CL_OUT") (pinfunction "CO_CL_OUT") (pintype "output"))
      (node (ref "U32") (pin "C_IN") (pinfunction "CI_C_IN") (pintype "input"))
    )
    (net (code "79") (name "Net-(U29-DO)") (class "Default")
      (node (ref "U29") (pin "D_OUT") (pinfunction "DO_D_OUT") (pintype "output"))
      (node (ref "U32") (pin "D_IN") (pinfunction "DI_D_IN") (pintype "input"))
    )
    (net (code "80") (name "Net-(U30-CO)") (class "Default")
      (node (ref "U30") (pin "CL_OUT") (pinfunction "CO_CL_OUT") (pintype "output"))
      (node (ref "U33") (pin "C_IN") (pinfunction "CI_C_IN") (pintype "input"))
    )
    (net (code "81") (name "Net-(U30-DO)") (class "Default")
      (node (ref "U30") (pin "D_OUT") (pinfunction "DO_D_OUT") (pintype "output"))
      (node (ref "U33") (pin "D_IN") (pinfunction "DI_D_IN") (pintype "input"))
    )
    (net (code "82") (name "Net-(U34-PB6(XTAL1))") (class "Default")
      (node (ref "R11") (pin "2") (pinfunction "2_2") (pintype "passive"))
      (node (ref "U34") (pin "7") (pinfunction "PB6(XTAL1)_7") (pintype "bidirectional"))
      (node (ref "Y1") (pin "1") (pinfunction "1_1") (pintype "passive"))
    )
    (net (code "83") (name "Net-(U34-PB7(XTAL2))") (class "Default")
      (node (ref "R11") (pin "1") (pinfunction "1_1") (pintype "passive"))
      (node (ref "U34") (pin "8") (pinfunction "PB7(XTAL2)_8") (pintype "bidirectional"))
      (node (ref "Y1") (pin "3") (pinfunction "3_3") (pintype "passive"))
    )
    (net (code "84") (name "POWER_INPUT") (class "Default")
      (node (ref "BAT1") (pin "+") (pinfunction "+_+") (pintype "passive"))
      (node (ref "C1") (pin "A") (pinfunction "+_A") (pintype "passive"))
      (node (ref "D1") (pin "C") (pinfunction "C_C") (pintype "passive"))
      (node (ref "L1") (pin "P$1") (pinfunction "1_P$1") (pintype "passive"))
      (node (ref "R3") (pin "2") (pinfunction "2_2") (pintype "passive"))
      (node (ref "R4") (pin "2") (pinfunction "2_2") (pintype "passive"))
      (node (ref "T1") (pin "E") (pinfunction "E_E") (pintype "passive"))
    )
    (net (code "85") (name "RST") (class "Default")
      (node (ref "C9") (pin "2") (pinfunction "2_2") (pintype "passive"))
      (node (ref "ICSP") (pin "5") (pinfunction "VBATT_5") (pintype "power_in"))
      (node (ref "R12") (pin "1") (pinfunction "1_1") (pintype "passive"))
      (node (ref "U34") (pin "29") (pinfunction "PC6(RESET)_29") (pintype "bidirectional"))
    )
    (net (code "86") (name "RXD") (class "Default")
      (node (ref "SERIAL") (pin "5") (pinfunction "VBATT_5") (pintype "power_in"))
      (node (ref "U34") (pin "30") (pinfunction "PD0(RXD)_30") (pintype "bidirectional"))
    )
    (net (code "87") (name "SCK") (class "Default")
      (node (ref "ICSP") (pin "3") (pinfunction "TXA_3") (pintype "output"))
      (node (ref "U3") (pin "C_IN") (pinfunction "CI_C_IN") (pintype "input"))
      (node (ref "U34") (pin "17") (pinfunction "PB5(SCK)_17") (pintype "bidirectional"))
    )
    (net (code "88") (name "SCL") (class "Default")
      (node (ref "Q3") (pin "3") (pinfunction "D_3") (pintype "bidirectional"))
      (node (ref "R17") (pin "1") (pinfunction "1_1") (pintype "passive"))
      (node (ref "U34") (pin "28") (pinfunction "PC5(ADC5)_28") (pintype "bidirectional"))
    )
    (net (code "89") (name "SDA") (class "Default")
      (node (ref "Q4") (pin "3") (pinfunction "D_3") (pintype "bidirectional"))
      (node (ref "R18") (pin "1") (pinfunction "1_1") (pintype "passive"))
      (node (ref "U34") (pin "27") (pinfunction "PC4(ADC4)_27") (pintype "bidirectional"))
    )
    (net (code "90") (name "SW") (class "Default")
      (node (ref "C3") (pin "2") (pinfunction "2_2") (pintype "passive"))
      (node (ref "D2") (pin "A") (pinfunction "A_A") (pintype "passive"))
      (node (ref "L1") (pin "P$2") (pinfunction "2_P$2") (pintype "passive"))
      (node (ref "U1") (pin "8") (pinfunction "SW_8") (pintype "passive"))
    )
    (net (code "91") (name "TXD") (class "Default")
      (node (ref "SERIAL") (pin "4") (pinfunction "RXA_4") (pintype "input"))
      (node (ref "U34") (pin "31") (pinfunction "PD1(TXD)_31") (pintype "bidirectional"))
    )
    (net (code "92") (name "unconnected-(U6-CO-PadCL_OUT)") (class "Default")
      (node (ref "U6") (pin "CL_OUT") (pinfunction "CO_CL_OUT") (pintype "output"))
    )
    (net (code "93") (name "unconnected-(U6-DO-PadD_OUT)") (class "Default")
      (node (ref "U6") (pin "D_OUT") (pinfunction "DO_D_OUT") (pintype "output"))
    )
    (net (code "94") (name "unconnected-(U34-ADC6-Pad19)") (class "Default")
      (node (ref "U34") (pin "19") (pinfunction "ADC6_19") (pintype "bidirectional"))
    )
    (net (code "95") (name "unconnected-(U34-ADC7-Pad22)") (class "Default")
      (node (ref "U34") (pin "22") (pinfunction "ADC7_22") (pintype "bidirectional"))
    )
    (net (code "96") (name "unconnected-(U34-PB0(ICP1)-Pad12)") (class "Default")
      (node (ref "U34") (pin "12") (pinfunction "PB0(ICP1)_12") (pintype "bidirectional"))
    )
    (net (code "97") (name "unconnected-(U34-PB1(OC1A)-Pad13)") (class "Default")
      (node (ref "U34") (pin "13") (pinfunction "PB1(OC1A)_13") (pintype "bidirectional"))
    )
    (net (code "98") (name "unconnected-(U34-PB2(SS{slash}OC1B)-Pad14)") (class "Default")
      (node (ref "U34") (pin "14") (pinfunction "PB2(SS/OC1B)_14") (pintype "bidirectional"))
    )
    (net (code "99") (name "unconnected-(U34-PC0(ADC0)-Pad23)") (class "Default")
      (node (ref "U34") (pin "23") (pinfunction "PC0(ADC0)_23") (pintype "bidirectional"))
    )
    (net (code "100") (name "unconnected-(U34-PC1(ADC1)-Pad24)") (class "Default")
      (node (ref "U34") (pin "24") (pinfunction "PC1(ADC1)_24") (pintype "bidirectional"))
    )
    (net (code "101") (name "unconnected-(U34-PC2(ADC2)-Pad25)") (class "Default")
      (node (ref "U34") (pin "25") (pinfunction "PC2(ADC2)_25") (pintype "bidirectional"))
    )
    (net (code "102") (name "unconnected-(U34-PC3(ADC3)-Pad26)") (class "Default")
      (node (ref "U34") (pin "26") (pinfunction "PC3(ADC3)_26") (pintype "bidirectional"))
    )
    (net (code "103") (name "unconnected-(U34-PD3(INT1)-Pad1)") (class "Default")
      (node (ref "U34") (pin "1") (pinfunction "PD3(INT1)_1") (pintype "bidirectional"))
    )
    (net (code "104") (name "unconnected-(U34-PD5(T1)-Pad9)") (class "Default")
      (node (ref "U34") (pin "9") (pinfunction "PD5(T1)_9") (pintype "bidirectional"))
    )
    (net (code "105") (name "unconnected-(U34-PD6(AIN0)-Pad10)") (class "Default")
      (node (ref "U34") (pin "10") (pinfunction "PD6(AIN0)_10") (pintype "bidirectional"))
    )
    (net (code "106") (name "unconnected-(U34-PD7(AIN1)-Pad11)") (class "Default")
      (node (ref "U34") (pin "11") (pinfunction "PD7(AIN1)_11") (pintype "bidirectional"))
    )
  )
)
